# MainController.net
KiCad netlist of a schematic drawn in Altium Designer
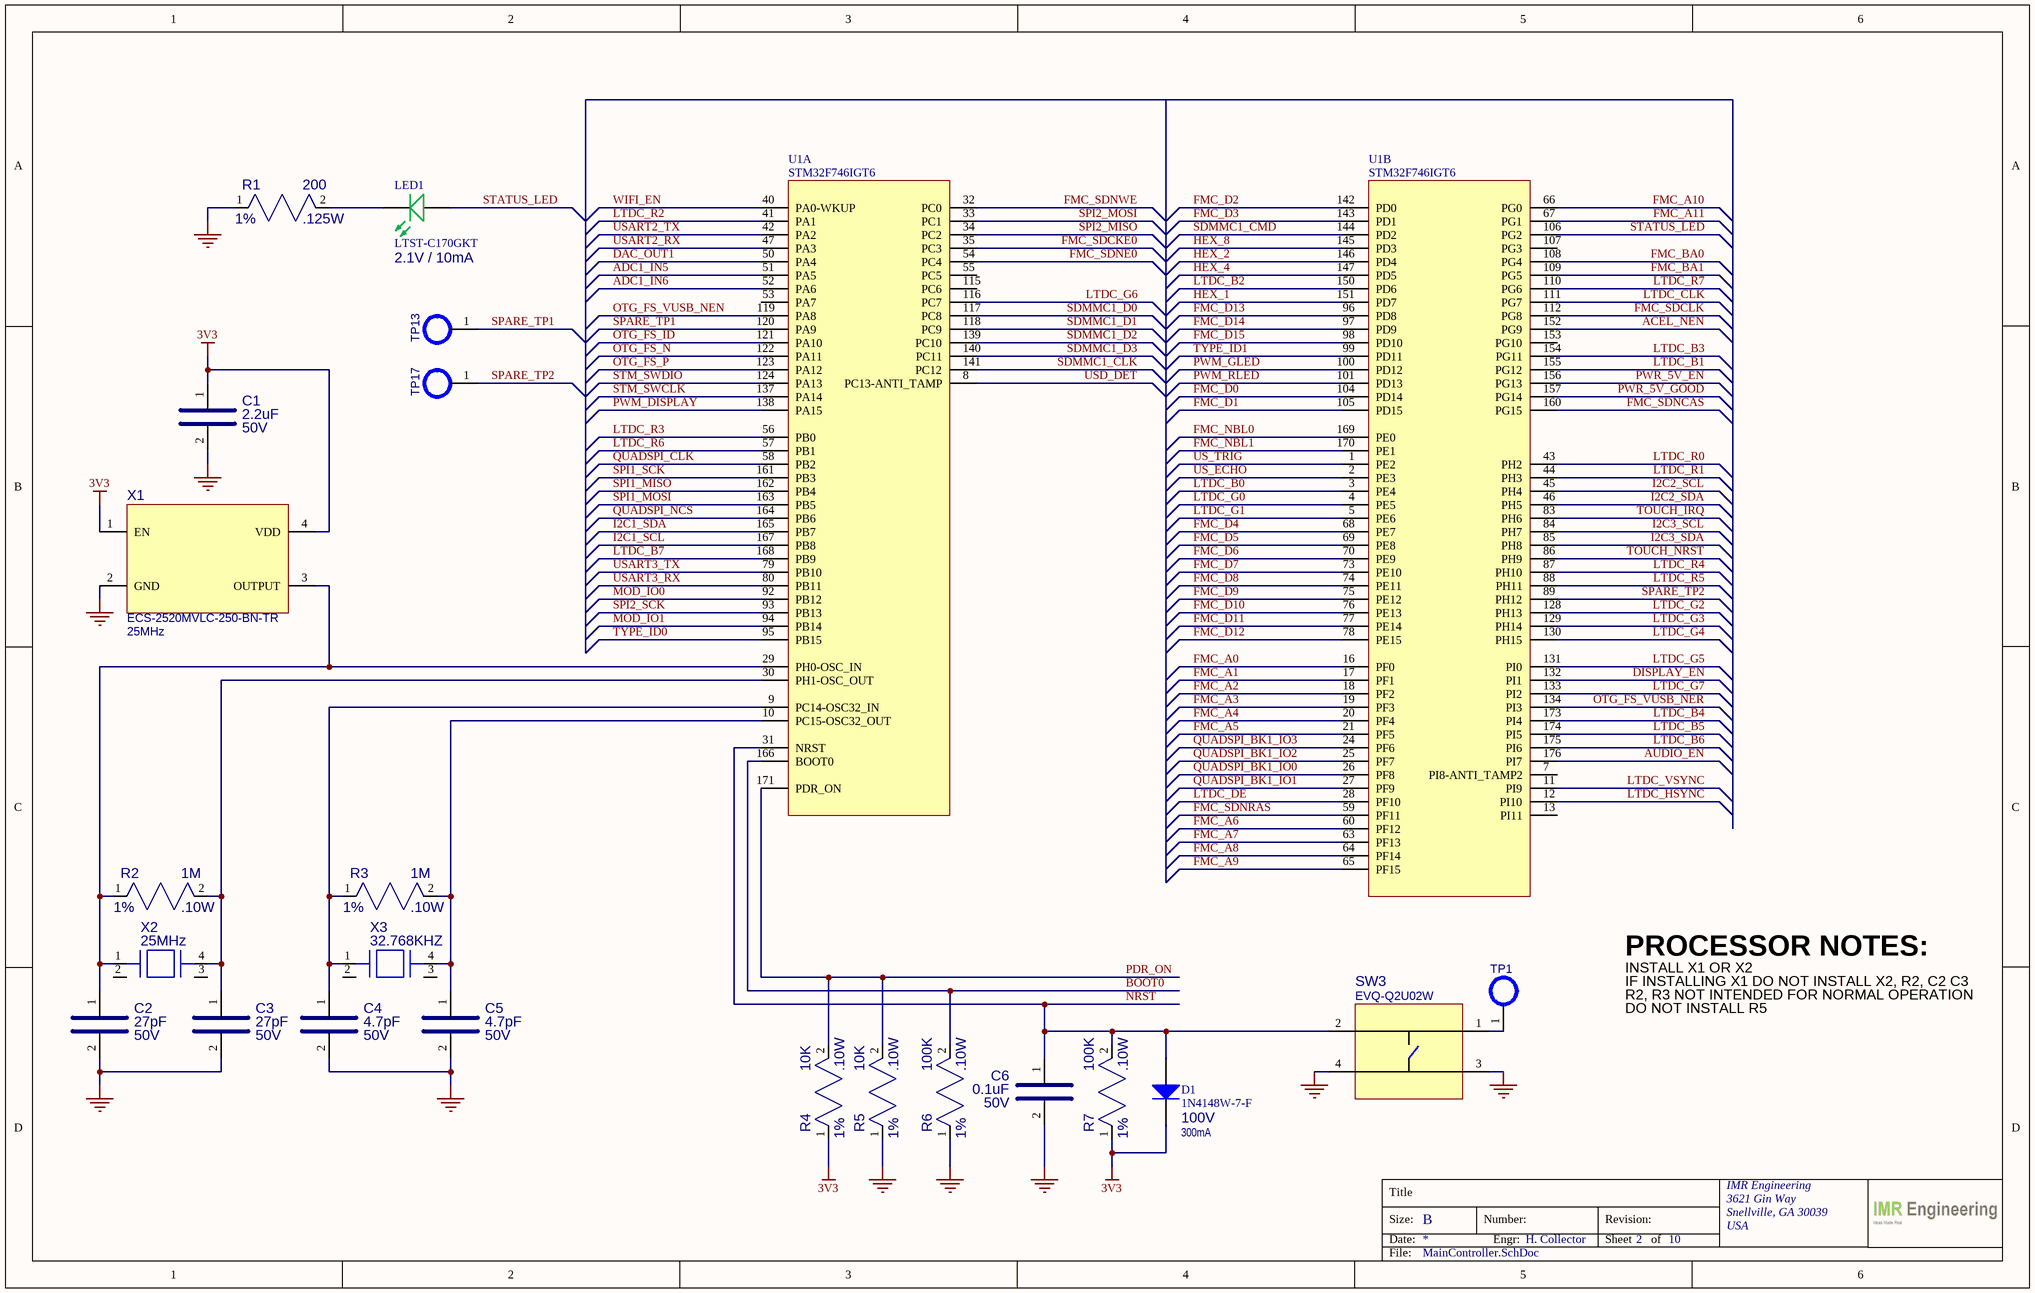
[diagram p0: MainController.SchDoc]

(export (version "E")
  (design (tool "Eeschema 10.0.6"))
  (components
    (comp (ref "C1")
      (value "2.2uF")
      (footprint "CAP_0805")
      (description "CAP CER 2.2UF 50V X7R 0805")
      (fields
        (field (name "MFG") "Taiyo Yuden")
        (field (name "TOLERANCE") "20%")
        (field (name "VOLTAGE") "50V")
      )
      (libsource (lib "IMR_Lib") (part "CAP_2.2UF_50V_0805"))
    )
    (comp (ref "C2")
      (value "27pF")
      (footprint "CAP_0603")
      (description "CAP CER 4.7PF 50V C0G/NPO 0603")
      (fields (field (name "MFG") "Yageo") (field (name "TOLERANCE") "10%") (field (name "VOLTAGE") "50V"))
      (libsource (lib "IMR_Lib") (part "CAP_27PF_50V_0603"))
    )
    (comp (ref "C3")
      (value "27pF")
      (footprint "CAP_0603")
      (description "CAP CER 4.7PF 50V C0G/NPO 0603")
      (fields (field (name "MFG") "Yageo") (field (name "TOLERANCE") "10%") (field (name "VOLTAGE") "50V"))
      (libsource (lib "IMR_Lib") (part "CAP_27PF_50V_0603"))
    )
    (comp (ref "C4")
      (value "4.7pF")
      (footprint "CAP_0603")
      (description "CAP CER 4.7PF 50V C0G/NPO 0603")
      (fields
        (field (name "MFG") "Yageo")
        (field (name "TOLERANCE") "+/-.25pF")
        (field (name "VOLTAGE") "50V")
      )
      (libsource (lib "IMR_Lib") (part "CAP_4.7PF_50V_0603"))
    )
    (comp (ref "C5")
      (value "4.7pF")
      (footprint "CAP_0603")
      (description "CAP CER 4.7PF 50V C0G/NPO 0603")
      (fields
        (field (name "MFG") "Yageo")
        (field (name "TOLERANCE") "+/-.25pF")
        (field (name "VOLTAGE") "50V")
      )
      (libsource (lib "IMR_Lib") (part "CAP_4.7PF_50V_0603"))
    )
    (comp (ref "C6")
      (value "0.1uF")
      (footprint "CAP_0603")
      (description "CAP CER 0.1UF 50V X7R 0603")
      (fields (field (name "MFG") "Yageo") (field (name "TOLERANCE") "10%") (field (name "VOLTAGE") "50V"))
      (libsource (lib "IMR_Lib") (part "CAP_0.1UF_50V_0603"))
    )
    (comp (ref "D1")
      (value "100V")
      (footprint "SOD123")
      (description "DIODE GEN PURP 100V 300MA SOD123")
      (fields
        (field (name "MFG") "Diodes Incorporated")
        (field (name "MFG_PN") "1N4148W-7-F")
        (field (name "CURRENT") "300mA")
        (field (name "Comment") "1N4148W-7-F")
      )
      (libsource (lib "IMR_Lib") (part "DIODE_1N4148W-7-F"))
    )
    (comp (ref "LED1")
      (value "2.1V / 10mA")
      (footprint "PMG_LTST-C170GKT")
      (description "DIODE, LED GREEN CLEAR SMD")
      (fields
        (field (name "MFG") "Lite-On Inc.")
        (field (name "MFG_PN") "LTST-C170GKT")
        (field (name "Comment") "LTST-C170GKT")
      )
      (libsource (lib "IMR_Lib") (part "DIODE_LED_GREEN_LTST-C170GKT"))
    )
    (comp (ref "R1")
      (value "200")
      (footprint "RES_0805")
      (description "RES SMD 200 OHM 1% 1/8W 0805")
      (fields
        (field (name "MFG") "Yageo")
        (field (name "TOLERANCE") "1%")
        (field (name "POWER") ".125W")
        (field (name "Comment") "RC0805FR-07200RL")
      )
      (libsource (lib "IMR_Lib") (part "RES_200_0805_1/8W_1%_1"))
    )
    (comp (ref "R2")
      (value "1M")
      (footprint "RES_0603")
      (description "RES SMD 1M OHM 1% 1/10W 0603")
      (fields
        (field (name "MFG") "Yageo")
        (field (name "TOLERANCE") "1%")
        (field (name "POWER") ".10W")
        (field (name "Comment") "RC0603FR-071ML")
      )
      (libsource (lib "IMR_Lib") (part "RES_1M_0603_1/10W_1%"))
    )
    (comp (ref "R3")
      (value "1M")
      (footprint "RES_0603")
      (description "RES SMD 1M OHM 1% 1/10W 0603")
      (fields
        (field (name "MFG") "Yageo")
        (field (name "TOLERANCE") "1%")
        (field (name "POWER") ".10W")
        (field (name "Comment") "RC0603FR-071ML")
      )
      (libsource (lib "IMR_Lib") (part "RES_1M_0603_1/10W_1%"))
    )
    (comp (ref "R4")
      (value "10K")
      (footprint "RES_0603")
      (description "RES SMD 10K OHM 1% 1/10W 0603")
      (fields
        (field (name "MFG") "Yageo")
        (field (name "TOLERANCE") "1%")
        (field (name "POWER") ".10W")
        (field (name "Comment") "RC0603FR-0710KL")
      )
      (libsource (lib "IMR_Lib") (part "RES_10K_0603_1/10W_1%"))
    )
    (comp (ref "R5")
      (value "10K")
      (footprint "RES_0603")
      (description "RES SMD 10K OHM 1% 1/10W 0603")
      (fields
        (field (name "MFG") "Yageo")
        (field (name "TOLERANCE") "1%")
        (field (name "POWER") ".10W")
        (field (name "Comment") "RC0603FR-0710KL")
      )
      (libsource (lib "IMR_Lib") (part "RES_10K_0603_1/10W_1%"))
    )
    (comp (ref "R6")
      (value "100K")
      (footprint "RES_0603")
      (description "RES SMD 100K OHM 1% 1/10W 0603")
      (fields
        (field (name "MFG") "Yageo")
        (field (name "TOLERANCE") "1%")
        (field (name "POWER") ".10W")
        (field (name "Comment") "RC0603FR-07100KL")
      )
      (libsource (lib "IMR_Lib") (part "RES_100K_0603_1/10W_1%"))
    )
    (comp (ref "R7")
      (value "100K")
      (footprint "RES_0603")
      (description "RES SMD 100K OHM 1% 1/10W 0603")
      (fields
        (field (name "MFG") "Yageo")
        (field (name "TOLERANCE") "1%")
        (field (name "POWER") ".10W")
        (field (name "Comment") "RC0603FR-07100KL")
      )
      (libsource (lib "IMR_Lib") (part "RES_100K_0603_1/10W_1%"))
    )
    (comp (ref "SW3")
      (value "EVQ-Q2U02W")
      (footprint "SW_EVQ-Q2U02W")
      (description "SWITCH TACTILE SPST-NO 0.02A 15V")
      (fields (field (name "MFG") "Panasonic Electronic Components") (field (name "MFG_PN") "EVQ-Q2U02W"))
      (libsource (lib "IMR_Lib") (part "SWITCH_EVQ-Q2U02W"))
    )
    (comp (ref "TP1")
      (value "TP_0635MM_HOLE")
      (footprint "TP_0635MM_HOLE")
      (description "3MM IN D. MT HOLE")
      (libsource (lib "IMR_Lib") (part "TP_0635MM_HOLE"))
    )
    (comp (ref "TP13")
      (value "TP_0635MM_HOLE")
      (footprint "TP_0635MM_HOLE")
      (description "3MM IN D. MT HOLE")
      (libsource (lib "IMR_Lib") (part "TP_0635MM_HOLE"))
    )
    (comp (ref "TP17")
      (value "TP_0635MM_HOLE")
      (footprint "TP_0635MM_HOLE")
      (description "3MM IN D. MT HOLE")
      (libsource (lib "IMR_Lib") (part "TP_0635MM_HOLE"))
    )
    (comp (ref "U1")
      (value "STM32F746IGT6")
      (footprint "QFP50P2600X2600X160-176N")
      (description "STM32F746NGH6 (STM32F7 Birdie) TBGA216")
      (fields (field (name "MFG") "STMicroelectronics"))
      (libsource (lib "IMR_Lib") (part "IC_STM32F746NGH6U"))
    )
    (comp (ref "X1")
      (value "25MHz")
      (footprint "OSC_ECS-2520S25-250-FN-TR")
      (description "XTAL OSC XO 25MHZ CMOS SMD")
      (fields
        (field (name "MFG") "ECS Inc.")
        (field (name "MFG_PN") "ECS-2520MVLC-250-BN-TR")
        (field (name "Comment") "ECS-2520MVLC-250-BN-TR")
      )
      (libsource (lib "IMR_Lib") (part "IC_OSC_ECS-2520MVLC-250-BN-TR"))
    )
    (comp (ref "X2")
      (value "25MHz")
      (footprint "XTAL_ECS")
      (description "CRYSTAL 25.0000MHZ 18PF SMD")
      (fields (field (name "MFG") "ECS Inc.") (field (name "TOLERANCE") "30PPM"))
      (libsource (lib "IMR_Lib") (part "XTAL_25HZ_6PF_SMD"))
    )
    (comp (ref "X3")
      (value "32.768KHZ")
      (footprint "XTAL_ECS-.327-6-17X-TR")
      (description "CRYSTAL 32.7680KHZ 6PF SMD")
      (fields (field (name "MFG") "EPSON") (field (name "TOLERANCE") "100ppm"))
      (libsource (lib "IMR_Lib") (part "XTAL_32.768KHZ_6PF_SMD"))
    )
  )
  (nets
    (net (code "1") (name "/ACEL_NEN") (class "Default")
      (node (ref "U1") (pin "152") (pinfunction "PG9_152") (pintype "passive"))
    )
    (net (code "2") (name "/ADC1_IN5") (class "Default")
      (node (ref "U1") (pin "51") (pinfunction "PA5_51") (pintype "passive"))
    )
    (net (code "3") (name "/ADC1_IN6") (class "Default")
      (node (ref "U1") (pin "52") (pinfunction "PA6_52") (pintype "passive"))
    )
    (net (code "4") (name "/AUDIO_EN") (class "Default")
      (node (ref "U1") (pin "176") (pinfunction "PI7_176") (pintype "passive"))
    )
    (net (code "5") (name "/BOOT0") (class "Default")
      (node (ref "R6") (pin "2") (pinfunction "2_2") (pintype "passive"))
      (node (ref "U1") (pin "166") (pinfunction "BOOT0_166") (pintype "passive"))
    )
    (net (code "6") (name "/DAC_OUT1") (class "Default")
      (node (ref "U1") (pin "50") (pinfunction "PA4_50") (pintype "passive"))
    )
    (net (code "7") (name "/DISPLAY_EN") (class "Default")
      (node (ref "U1") (pin "132") (pinfunction "PI1_132") (pintype "passive"))
    )
    (net (code "8") (name "/FMC_A0") (class "Default")
      (node (ref "U1") (pin "16") (pinfunction "PF0_16") (pintype "passive"))
    )
    (net (code "9") (name "/FMC_A1") (class "Default")
      (node (ref "U1") (pin "17") (pinfunction "PF1_17") (pintype "passive"))
    )
    (net (code "10") (name "/FMC_A2") (class "Default")
      (node (ref "U1") (pin "18") (pinfunction "PF2_18") (pintype "passive"))
    )
    (net (code "11") (name "/FMC_A3") (class "Default")
      (node (ref "U1") (pin "19") (pinfunction "PF3_19") (pintype "passive"))
    )
    (net (code "12") (name "/FMC_A4") (class "Default")
      (node (ref "U1") (pin "20") (pinfunction "PF4_20") (pintype "passive"))
    )
    (net (code "13") (name "/FMC_A5") (class "Default")
      (node (ref "U1") (pin "21") (pinfunction "PF5_21") (pintype "passive"))
    )
    (net (code "14") (name "/FMC_A6") (class "Default")
      (node (ref "U1") (pin "60") (pinfunction "PF12_60") (pintype "passive"))
    )
    (net (code "15") (name "/FMC_A7") (class "Default")
      (node (ref "U1") (pin "63") (pinfunction "PF13_63") (pintype "passive"))
    )
    (net (code "16") (name "/FMC_A8") (class "Default")
      (node (ref "U1") (pin "64") (pinfunction "PF14_64") (pintype "passive"))
    )
    (net (code "17") (name "/FMC_A9") (class "Default")
      (node (ref "U1") (pin "65") (pinfunction "PF15_65") (pintype "passive"))
    )
    (net (code "18") (name "/FMC_A10") (class "Default")
      (node (ref "U1") (pin "66") (pinfunction "PG0_66") (pintype "passive"))
    )
    (net (code "19") (name "/FMC_A11") (class "Default")
      (node (ref "U1") (pin "67") (pinfunction "PG1_67") (pintype "passive"))
    )
    (net (code "20") (name "/FMC_BA0") (class "Default")
      (node (ref "U1") (pin "108") (pinfunction "PG4_108") (pintype "passive"))
    )
    (net (code "21") (name "/FMC_BA1") (class "Default")
      (node (ref "U1") (pin "109") (pinfunction "PG5_109") (pintype "passive"))
    )
    (net (code "22") (name "/FMC_D0") (class "Default")
      (node (ref "U1") (pin "104") (pinfunction "PD14_104") (pintype "passive"))
    )
    (net (code "23") (name "/FMC_D1") (class "Default")
      (node (ref "U1") (pin "105") (pinfunction "PD15_105") (pintype "passive"))
    )
    (net (code "24") (name "/FMC_D2") (class "Default")
      (node (ref "U1") (pin "142") (pinfunction "PD0_142") (pintype "passive"))
    )
    (net (code "25") (name "/FMC_D3") (class "Default")
      (node (ref "U1") (pin "143") (pinfunction "PD1_143") (pintype "passive"))
    )
    (net (code "26") (name "/FMC_D4") (class "Default")
      (node (ref "U1") (pin "68") (pinfunction "PE7_68") (pintype "passive"))
    )
    (net (code "27") (name "/FMC_D5") (class "Default")
      (node (ref "U1") (pin "69") (pinfunction "PE8_69") (pintype "passive"))
    )
    (net (code "28") (name "/FMC_D6") (class "Default")
      (node (ref "U1") (pin "70") (pinfunction "PE9_70") (pintype "passive"))
    )
    (net (code "29") (name "/FMC_D7") (class "Default")
      (node (ref "U1") (pin "73") (pinfunction "PE10_73") (pintype "passive"))
    )
    (net (code "30") (name "/FMC_D8") (class "Default")
      (node (ref "U1") (pin "74") (pinfunction "PE11_74") (pintype "passive"))
    )
    (net (code "31") (name "/FMC_D9") (class "Default")
      (node (ref "U1") (pin "75") (pinfunction "PE12_75") (pintype "passive"))
    )
    (net (code "32") (name "/FMC_D10") (class "Default")
      (node (ref "U1") (pin "76") (pinfunction "PE13_76") (pintype "passive"))
    )
    (net (code "33") (name "/FMC_D11") (class "Default")
      (node (ref "U1") (pin "77") (pinfunction "PE14_77") (pintype "passive"))
    )
    (net (code "34") (name "/FMC_D12") (class "Default")
      (node (ref "U1") (pin "78") (pinfunction "PE15_78") (pintype "passive"))
    )
    (net (code "35") (name "/FMC_D13") (class "Default")
      (node (ref "U1") (pin "96") (pinfunction "PD8_96") (pintype "passive"))
    )
    (net (code "36") (name "/FMC_D14") (class "Default")
      (node (ref "U1") (pin "97") (pinfunction "PD9_97") (pintype "passive"))
    )
    (net (code "37") (name "/FMC_D15") (class "Default")
      (node (ref "U1") (pin "98") (pinfunction "PD10_98") (pintype "passive"))
    )
    (net (code "38") (name "/FMC_NBL0") (class "Default")
      (node (ref "U1") (pin "169") (pinfunction "PE0_169") (pintype "passive"))
    )
    (net (code "39") (name "/FMC_NBL1") (class "Default")
      (node (ref "U1") (pin "170") (pinfunction "PE1_170") (pintype "passive"))
    )
    (net (code "40") (name "/FMC_SDCKE0") (class "Default")
      (node (ref "U1") (pin "35") (pinfunction "PC3_35") (pintype "passive"))
    )
    (net (code "41") (name "/FMC_SDCLK") (class "Default")
      (node (ref "U1") (pin "112") (pinfunction "PG8_112") (pintype "passive"))
    )
    (net (code "42") (name "/FMC_SDNCAS") (class "Default")
      (node (ref "U1") (pin "160") (pinfunction "PG15_160") (pintype "passive"))
    )
    (net (code "43") (name "/FMC_SDNE0") (class "Default")
      (node (ref "U1") (pin "54") (pinfunction "PC4_54") (pintype "passive"))
    )
    (net (code "44") (name "/FMC_SDNRAS") (class "Default")
      (node (ref "U1") (pin "59") (pinfunction "PF11_59") (pintype "passive"))
    )
    (net (code "45") (name "/FMC_SDNWE") (class "Default")
      (node (ref "U1") (pin "32") (pinfunction "PC0_32") (pintype "passive"))
    )
    (net (code "46") (name "/HEX_1") (class "Default")
      (node (ref "U1") (pin "151") (pinfunction "PD7_151") (pintype "passive"))
    )
    (net (code "47") (name "/HEX_2") (class "Default")
      (node (ref "U1") (pin "146") (pinfunction "PD4_146") (pintype "passive"))
    )
    (net (code "48") (name "/HEX_4") (class "Default")
      (node (ref "U1") (pin "147") (pinfunction "PD5_147") (pintype "passive"))
    )
    (net (code "49") (name "/HEX_8") (class "Default")
      (node (ref "U1") (pin "145") (pinfunction "PD3_145") (pintype "passive"))
    )
    (net (code "50") (name "/I2C1_SCL") (class "Default")
      (node (ref "U1") (pin "167") (pinfunction "PB8_167") (pintype "passive"))
    )
    (net (code "51") (name "/I2C1_SDA") (class "Default")
      (node (ref "U1") (pin "165") (pinfunction "PB7_165") (pintype "passive"))
    )
    (net (code "52") (name "/I2C2_SCL") (class "Default")
      (node (ref "U1") (pin "45") (pinfunction "PH4_45") (pintype "passive"))
    )
    (net (code "53") (name "/I2C2_SDA") (class "Default")
      (node (ref "U1") (pin "46") (pinfunction "PH5_46") (pintype "passive"))
    )
    (net (code "54") (name "/I2C3_SCL") (class "Default")
      (node (ref "U1") (pin "84") (pinfunction "PH7_84") (pintype "passive"))
    )
    (net (code "55") (name "/I2C3_SDA") (class "Default")
      (node (ref "U1") (pin "85") (pinfunction "PH8_85") (pintype "passive"))
    )
    (net (code "56") (name "/LTDC_B0") (class "Default")
      (node (ref "U1") (pin "3") (pinfunction "PE4_3") (pintype "passive"))
    )
    (net (code "57") (name "/LTDC_B1") (class "Default")
      (node (ref "U1") (pin "155") (pinfunction "PG12_155") (pintype "passive"))
    )
    (net (code "58") (name "/LTDC_B2") (class "Default")
      (node (ref "U1") (pin "150") (pinfunction "PD6_150") (pintype "passive"))
    )
    (net (code "59") (name "/LTDC_B3") (class "Default")
      (node (ref "U1") (pin "154") (pinfunction "PG11_154") (pintype "passive"))
    )
    (net (code "60") (name "/LTDC_B4") (class "Default")
      (node (ref "U1") (pin "173") (pinfunction "PI4_173") (pintype "passive"))
    )
    (net (code "61") (name "/LTDC_B5") (class "Default")
      (node (ref "U1") (pin "174") (pinfunction "PI5_174") (pintype "passive"))
    )
    (net (code "62") (name "/LTDC_B6") (class "Default")
      (node (ref "U1") (pin "175") (pinfunction "PI6_175") (pintype "passive"))
    )
    (net (code "63") (name "/LTDC_B7") (class "Default")
      (node (ref "U1") (pin "168") (pinfunction "PB9_168") (pintype "passive"))
    )
    (net (code "64") (name "/LTDC_CLK") (class "Default")
      (node (ref "U1") (pin "111") (pinfunction "PG7_111") (pintype "passive"))
    )
    (net (code "65") (name "/LTDC_DE") (class "Default")
      (node (ref "U1") (pin "28") (pinfunction "PF10_28") (pintype "passive"))
    )
    (net (code "66") (name "/LTDC_G0") (class "Default")
      (node (ref "U1") (pin "4") (pinfunction "PE5_4") (pintype "passive"))
    )
    (net (code "67") (name "/LTDC_G1") (class "Default")
      (node (ref "U1") (pin "5") (pinfunction "PE6_5") (pintype "passive"))
    )
    (net (code "68") (name "/LTDC_G2") (class "Default")
      (node (ref "U1") (pin "128") (pinfunction "PH13_128") (pintype "passive"))
    )
    (net (code "69") (name "/LTDC_G3") (class "Default")
      (node (ref "U1") (pin "129") (pinfunction "PH14_129") (pintype "passive"))
    )
    (net (code "70") (name "/LTDC_G4") (class "Default")
      (node (ref "U1") (pin "130") (pinfunction "PH15_130") (pintype "passive"))
    )
    (net (code "71") (name "/LTDC_G5") (class "Default")
      (node (ref "U1") (pin "131") (pinfunction "PI0_131") (pintype "passive"))
    )
    (net (code "72") (name "/LTDC_G6") (class "Default")
      (node (ref "U1") (pin "116") (pinfunction "PC7_116") (pintype "passive"))
    )
    (net (code "73") (name "/LTDC_G7") (class "Default")
      (node (ref "U1") (pin "133") (pinfunction "PI2_133") (pintype "passive"))
    )
    (net (code "74") (name "/LTDC_HSYNC") (class "Default")
      (node (ref "U1") (pin "12") (pinfunction "PI10_12") (pintype "passive"))
    )
    (net (code "75") (name "/LTDC_R0") (class "Default")
      (node (ref "U1") (pin "43") (pinfunction "PH2_43") (pintype "passive"))
    )
    (net (code "76") (name "/LTDC_R1") (class "Default")
      (node (ref "U1") (pin "44") (pinfunction "PH3_44") (pintype "passive"))
    )
    (net (code "77") (name "/LTDC_R2") (class "Default")
      (node (ref "U1") (pin "41") (pinfunction "PA1_41") (pintype "passive"))
    )
    (net (code "78") (name "/LTDC_R3") (class "Default")
      (node (ref "U1") (pin "56") (pinfunction "PB0_56") (pintype "passive"))
    )
    (net (code "79") (name "/LTDC_R4") (class "Default")
      (node (ref "U1") (pin "87") (pinfunction "PH10_87") (pintype "passive"))
    )
    (net (code "80") (name "/LTDC_R5") (class "Default")
      (node (ref "U1") (pin "88") (pinfunction "PH11_88") (pintype "passive"))
    )
    (net (code "81") (name "/LTDC_R6") (class "Default")
      (node (ref "U1") (pin "57") (pinfunction "PB1_57") (pintype "passive"))
    )
    (net (code "82") (name "/LTDC_R7") (class "Default")
      (node (ref "U1") (pin "110") (pinfunction "PG6_110") (pintype "passive"))
    )
    (net (code "83") (name "/LTDC_VSYNC") (class "Default")
      (node (ref "U1") (pin "11") (pinfunction "PI9_11") (pintype "passive"))
    )
    (net (code "84") (name "/MOD_IO0") (class "Default")
      (node (ref "U1") (pin "92") (pinfunction "PB12_92") (pintype "passive"))
    )
    (net (code "85") (name "/MOD_IO1") (class "Default")
      (node (ref "U1") (pin "94") (pinfunction "PB14_94") (pintype "passive"))
    )
    (net (code "86") (name "/NRST") (class "Default")
      (node (ref "C6") (pin "1") (pinfunction "1_1") (pintype "passive"))
      (node (ref "D1") (pin "1") (pinfunction "A_1") (pintype "passive"))
      (node (ref "R7") (pin "2") (pinfunction "2_2") (pintype "passive"))
      (node (ref "SW3") (pin "2") (pinfunction "B'_2") (pintype "passive"))
      (node (ref "U1") (pin "31") (pinfunction "NRST_31") (pintype "passive"))
    )
    (net (code "87") (name "/OTG_FS_ID") (class "Default")
      (node (ref "U1") (pin "121") (pinfunction "PA10_121") (pintype "passive"))
    )
    (net (code "88") (name "/OTG_FS_N") (class "Default")
      (node (ref "U1") (pin "122") (pinfunction "PA11_122") (pintype "passive"))
    )
    (net (code "89") (name "/OTG_FS_P") (class "Default")
      (node (ref "U1") (pin "123") (pinfunction "PA12_123") (pintype "passive"))
    )
    (net (code "90") (name "/OTG_FS_VUSB_NEN") (class "Default")
      (node (ref "U1") (pin "119") (pinfunction "PA8_119") (pintype "passive"))
    )
    (net (code "91") (name "/OTG_FS_VUSB_NER") (class "Default")
      (node (ref "U1") (pin "134") (pinfunction "PI3_134") (pintype "passive"))
    )
    (net (code "92") (name "/PDR_ON") (class "Default")
      (node (ref "R4") (pin "2") (pinfunction "2_2") (pintype "passive"))
      (node (ref "R5") (pin "2") (pinfunction "2_2") (pintype "passive"))
      (node (ref "U1") (pin "171") (pinfunction "PDR_ON_171") (pintype "passive"))
    )
    (net (code "93") (name "/PWM_DISPLAY") (class "Default")
      (node (ref "U1") (pin "138") (pinfunction "PA15_138") (pintype "passive"))
    )
    (net (code "94") (name "/PWM_GLED") (class "Default")
      (node (ref "U1") (pin "100") (pinfunction "PD12_100") (pintype "passive"))
    )
    (net (code "95") (name "/PWM_RLED") (class "Default")
      (node (ref "U1") (pin "101") (pinfunction "PD13_101") (pintype "passive"))
    )
    (net (code "96") (name "/PWR_5V_EN") (class "Default")
      (node (ref "U1") (pin "156") (pinfunction "PG13_156") (pintype "passive"))
    )
    (net (code "97") (name "/PWR_5V_GOOD") (class "Default")
      (node (ref "U1") (pin "157") (pinfunction "PG14_157") (pintype "passive"))
    )
    (net (code "98") (name "/QUADSPI_BK1_IO0") (class "Default")
      (node (ref "U1") (pin "26") (pinfunction "PF8_26") (pintype "passive"))
    )
    (net (code "99") (name "/QUADSPI_BK1_IO1") (class "Default")
      (node (ref "U1") (pin "27") (pinfunction "PF9_27") (pintype "passive"))
    )
    (net (code "100") (name "/QUADSPI_BK1_IO2") (class "Default")
      (node (ref "U1") (pin "25") (pinfunction "PF7_25") (pintype "passive"))
    )
    (net (code "101") (name "/QUADSPI_BK1_IO3") (class "Default")
      (node (ref "U1") (pin "24") (pinfunction "PF6_24") (pintype "passive"))
    )
    (net (code "102") (name "/QUADSPI_CLK") (class "Default")
      (node (ref "U1") (pin "58") (pinfunction "PB2_58") (pintype "passive"))
    )
    (net (code "103") (name "/QUADSPI_NCS") (class "Default")
      (node (ref "U1") (pin "164") (pinfunction "PB6_164") (pintype "passive"))
    )
    (net (code "104") (name "/SDMMC1_CLK") (class "Default")
      (node (ref "U1") (pin "141") (pinfunction "PC12_141") (pintype "passive"))
    )
    (net (code "105") (name "/SDMMC1_CMD") (class "Default")
      (node (ref "U1") (pin "144") (pinfunction "PD2_144") (pintype "passive"))
    )
    (net (code "106") (name "/SDMMC1_D0") (class "Default")
      (node (ref "U1") (pin "117") (pinfunction "PC8_117") (pintype "passive"))
    )
    (net (code "107") (name "/SDMMC1_D1") (class "Default")
      (node (ref "U1") (pin "118") (pinfunction "PC9_118") (pintype "passive"))
    )
    (net (code "108") (name "/SDMMC1_D2") (class "Default")
      (node (ref "U1") (pin "139") (pinfunction "PC10_139") (pintype "passive"))
    )
    (net (code "109") (name "/SDMMC1_D3") (class "Default")
      (node (ref "U1") (pin "140") (pinfunction "PC11_140") (pintype "passive"))
    )
    (net (code "110") (name "/SPARE_TP1") (class "Default")
      (node (ref "TP13") (pin "1") (pinfunction "1_1") (pintype "passive"))
      (node (ref "U1") (pin "120") (pinfunction "PA9_120") (pintype "passive"))
    )
    (net (code "111") (name "/SPARE_TP2") (class "Default")
      (node (ref "TP17") (pin "1") (pinfunction "1_1") (pintype "passive"))
      (node (ref "U1") (pin "89") (pinfunction "PH12_89") (pintype "passive"))
    )
    (net (code "112") (name "/SPI1_MISO") (class "Default")
      (node (ref "U1") (pin "162") (pinfunction "PB4_162") (pintype "passive"))
    )
    (net (code "113") (name "/SPI1_MOSI") (class "Default")
      (node (ref "U1") (pin "163") (pinfunction "PB5_163") (pintype "passive"))
    )
    (net (code "114") (name "/SPI1_SCK") (class "Default")
      (node (ref "U1") (pin "161") (pinfunction "PB3_161") (pintype "passive"))
    )
    (net (code "115") (name "/SPI2_MISO") (class "Default")
      (node (ref "U1") (pin "34") (pinfunction "PC2_34") (pintype "passive"))
    )
    (net (code "116") (name "/SPI2_MOSI") (class "Default")
      (node (ref "U1") (pin "33") (pinfunction "PC1_33") (pintype "passive"))
    )
    (net (code "117") (name "/SPI2_SCK") (class "Default")
      (node (ref "U1") (pin "93") (pinfunction "PB13_93") (pintype "passive"))
    )
    (net (code "118") (name "/STATUS_LED") (class "Default")
      (node (ref "LED1") (pin "1") (pinfunction "A_1") (pintype "passive"))
      (node (ref "U1") (pin "106") (pinfunction "PG2_106") (pintype "passive"))
    )
    (net (code "119") (name "/STM_SWCLK") (class "Default")
      (node (ref "U1") (pin "137") (pinfunction "PA14_137") (pintype "passive"))
    )
    (net (code "120") (name "/STM_SWDIO") (class "Default")
      (node (ref "U1") (pin "124") (pinfunction "PA13_124") (pintype "passive"))
    )
    (net (code "121") (name "/TOUCH_IRQ") (class "Default")
      (node (ref "U1") (pin "83") (pinfunction "PH6_83") (pintype "passive"))
    )
    (net (code "122") (name "/TOUCH_NRST") (class "Default")
      (node (ref "U1") (pin "86") (pinfunction "PH9_86") (pintype "passive"))
    )
    (net (code "123") (name "/TYPE_ID0") (class "Default")
      (node (ref "U1") (pin "95") (pinfunction "PB15_95") (pintype "passive"))
    )
    (net (code "124") (name "/TYPE_ID1") (class "Default")
      (node (ref "U1") (pin "99") (pinfunction "PD11_99") (pintype "passive"))
    )
    (net (code "125") (name "/USART2_RX") (class "Default")
      (node (ref "U1") (pin "47") (pinfunction "PA3_47") (pintype "passive"))
    )
    (net (code "126") (name "/USART2_TX") (class "Default")
      (node (ref "U1") (pin "42") (pinfunction "PA2_42") (pintype "passive"))
    )
    (net (code "127") (name "/USART3_RX") (class "Default")
      (node (ref "U1") (pin "80") (pinfunction "PB11_80") (pintype "passive"))
    )
    (net (code "128") (name "/USART3_TX") (class "Default")
      (node (ref "U1") (pin "79") (pinfunction "PB10_79") (pintype "passive"))
    )
    (net (code "129") (name "/USD_DET") (class "Default")
      (node (ref "U1") (pin "8") (pinfunction "PC13-ANTI_TAMP_8") (pintype "passive"))
    )
    (net (code "130") (name "/US_ECHO") (class "Default")
      (node (ref "U1") (pin "2") (pinfunction "PE3_2") (pintype "passive"))
    )
    (net (code "131") (name "/US_TRIG") (class "Default")
      (node (ref "U1") (pin "1") (pinfunction "PE2_1") (pintype "passive"))
    )
    (net (code "132") (name "/WIFI_EN") (class "Default")
      (node (ref "U1") (pin "40") (pinfunction "PA0-WKUP_40") (pintype "passive"))
    )
    (net (code "133") (name "3V3") (class "Default")
      (node (ref "C1") (pin "1") (pinfunction "1_1") (pintype "passive"))
      (node (ref "D1") (pin "2") (pinfunction "K_2") (pintype "passive"))
      (node (ref "R4") (pin "1") (pinfunction "1_1") (pintype "passive"))
      (node (ref "R7") (pin "1") (pinfunction "1_1") (pintype "passive"))
      (node (ref "X1") (pin "1") (pinfunction "EN_1") (pintype "passive"))
      (node (ref "X1") (pin "4") (pinfunction "VDD_4") (pintype "passive"))
    )
    (net (code "134") (name "GND") (class "Default")
      (node (ref "C1") (pin "2") (pinfunction "2_2") (pintype "passive"))
      (node (ref "C2") (pin "2") (pinfunction "2_2") (pintype "passive"))
      (node (ref "C3") (pin "2") (pinfunction "2_2") (pintype "passive"))
      (node (ref "C4") (pin "2") (pinfunction "2_2") (pintype "passive"))
      (node (ref "C5") (pin "2") (pinfunction "2_2") (pintype "passive"))
      (node (ref "C6") (pin "2") (pinfunction "2_2") (pintype "passive"))
      (node (ref "R1") (pin "1") (pinfunction "1_1") (pintype "passive"))
      (node (ref "R5") (pin "1") (pinfunction "1_1") (pintype "passive"))
      (node (ref "R6") (pin "1") (pinfunction "1_1") (pintype "passive"))
      (node (ref "SW3") (pin "3") (pinfunction "A_3") (pintype "passive"))
      (node (ref "SW3") (pin "4") (pinfunction "A'_4") (pintype "passive"))
      (node (ref "X1") (pin "2") (pinfunction "GND_2") (pintype "passive"))
    )
    (net (code "135") (name "Net-(LED1-K)") (class "Default")
      (node (ref "LED1") (pin "2") (pinfunction "K_2") (pintype "passive"))
      (node (ref "R1") (pin "2") (pinfunction "2_2") (pintype "passive"))
    )
    (net (code "136") (name "Net-(SW3-B)") (class "Default")
      (node (ref "SW3") (pin "1") (pinfunction "B_1") (pintype "passive"))
      (node (ref "TP1") (pin "1") (pinfunction "1_1") (pintype "passive"))
    )
    (net (code "137") (name "Net-(U1A-PC14-OSC32_IN)") (class "Default")
      (node (ref "C4") (pin "1") (pinfunction "1_1") (pintype "passive"))
      (node (ref "R3") (pin "1") (pinfunction "1_1") (pintype "passive"))
      (node (ref "U1") (pin "9") (pinfunction "PC14-OSC32_IN_9") (pintype "passive"))
      (node (ref "X3") (pin "1") (pinfunction "1_1") (pintype "passive"))
    )
    (net (code "138") (name "Net-(U1A-PC15-OSC32_OUT)") (class "Default")
      (node (ref "C5") (pin "1") (pinfunction "1_1") (pintype "passive"))
      (node (ref "R3") (pin "2") (pinfunction "2_2") (pintype "passive"))
      (node (ref "U1") (pin "10") (pinfunction "PC15-OSC32_OUT_10") (pintype "passive"))
      (node (ref "X3") (pin "4") (pinfunction "4_4") (pintype "passive"))
    )
    (net (code "139") (name "Net-(U1A-PH0-OSC_IN)") (class "Default")
      (node (ref "C2") (pin "1") (pinfunction "1_1") (pintype "passive"))
      (node (ref "R2") (pin "1") (pinfunction "1_1") (pintype "passive"))
      (node (ref "U1") (pin "29") (pinfunction "PH0-OSC_IN_29") (pintype "passive"))
      (node (ref "X1") (pin "3") (pinfunction "OUTPUT_3") (pintype "passive"))
      (node (ref "X2") (pin "1") (pinfunction "1_1") (pintype "passive"))
    )
    (net (code "140") (name "Net-(U1A-PH1-OSC_OUT)") (class "Default")
      (node (ref "C3") (pin "1") (pinfunction "1_1") (pintype "passive"))
      (node (ref "R2") (pin "2") (pinfunction "2_2") (pintype "passive"))
      (node (ref "U1") (pin "30") (pinfunction "PH1-OSC_OUT_30") (pintype "passive"))
      (node (ref "X2") (pin "4") (pinfunction "4_4") (pintype "passive"))
    )
    (net (code "141") (name "unconnected-(U1A-PA7-Pad53)") (class "Default")
      (node (ref "U1") (pin "53") (pinfunction "PA7_53") (pintype "passive"))
    )
    (net (code "142") (name "unconnected-(U1A-PC5-Pad55)") (class "Default")
      (node (ref "U1") (pin "55") (pinfunction "PC5_55") (pintype "passive"))
    )
    (net (code "143") (name "unconnected-(U1A-PC6-Pad115)") (class "Default")
      (node (ref "U1") (pin "115") (pinfunction "PC6_115") (pintype "passive"))
    )
    (net (code "144") (name "unconnected-(U1B-PG3-Pad107)") (class "Default")
      (node (ref "U1") (pin "107") (pinfunction "PG3_107") (pintype "passive"))
    )
    (net (code "145") (name "unconnected-(U1B-PG10-Pad153)") (class "Default")
      (node (ref "U1") (pin "153") (pinfunction "PG10_153") (pintype "passive"))
    )
    (net (code "146") (name "unconnected-(U1B-PI8-ANTI_TAMP2-Pad7)") (class "Default")
      (node (ref "U1") (pin "7") (pinfunction "PI8-ANTI_TAMP2_7") (pintype "passive"))
    )
    (net (code "147") (name "unconnected-(U1B-PI11-Pad13)") (class "Default")
      (node (ref "U1") (pin "13") (pinfunction "PI11_13") (pintype "passive"))
    )
    (net (code "148") (name "unconnected-(X2-Pad2)") (class "Default")
      (node (ref "X2") (pin "2") (pinfunction "2_2") (pintype "passive"))
    )
    (net (code "149") (name "unconnected-(X2-Pad3)") (class "Default")
      (node (ref "X2") (pin "3") (pinfunction "3_3") (pintype "passive"))
    )
    (net (code "150") (name "unconnected-(X3-Pad2)") (class "Default")
      (node (ref "X3") (pin "2") (pinfunction "2_2") (pintype "passive"))
    )
    (net (code "151") (name "unconnected-(X3-Pad3)") (class "Default")
      (node (ref "X3") (pin "3") (pinfunction "3_3") (pintype "passive"))
    )
  )
)
